# ProPrj_1111_2025-11-28.net
KiCad netlist of a schematic drawn in EasyEDA Pro
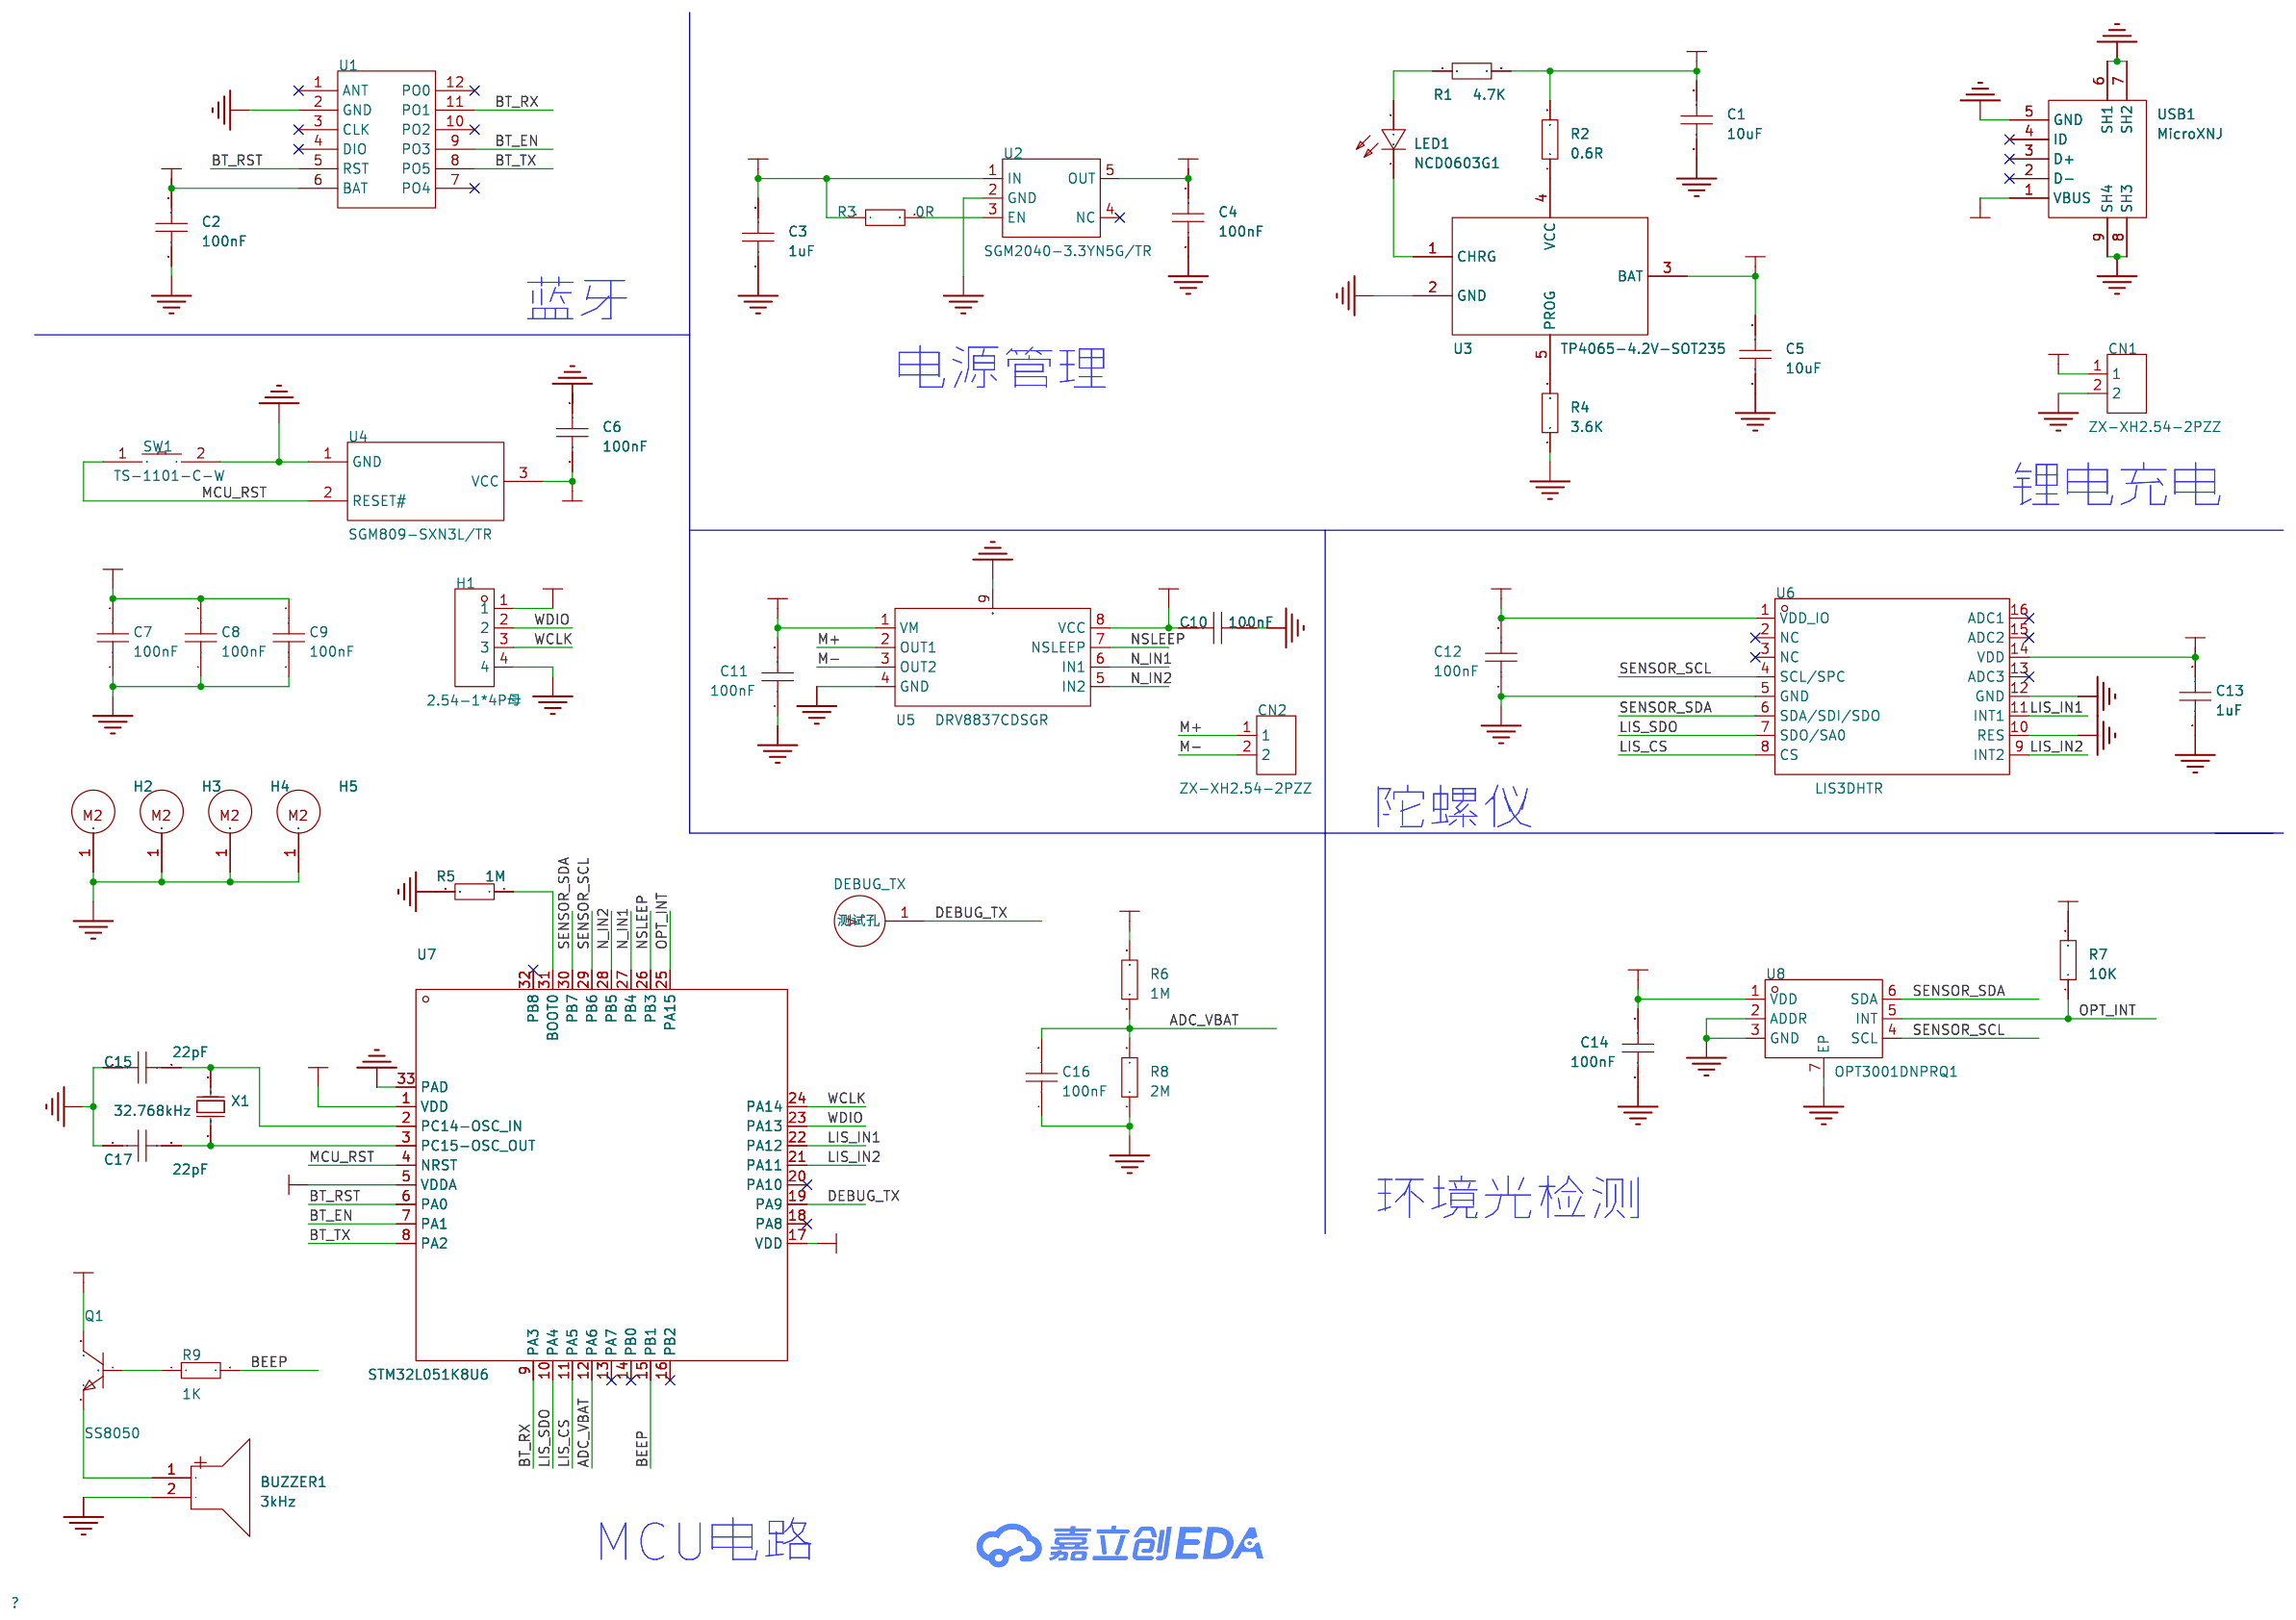
[diagram p0: schematic sheet]

(export (version "E")
  (design (tool "Eeschema 10.0.6"))
  (components
    (comp (ref "BUZZER1")
      (value "3kHz")
      (footprint "easyedapro:BUZ-TH_BD9.0-P5.00-D0.6-FD")
      (description "驱动方式:有源(内含驱动线路);构造类型:电磁式;频率:3kHz;声压(SPL):85dB;")
      (fields (field (name "Manufacturer Part") "HNB09A03") (field (name "Manufacturer") "华能"))
      (libsource (lib "easyedapro") (part "HNB09A03"))
    )
    (comp (ref "C1")
      (value "10uF")
      (footprint "easyedapro:C0603")
      (libsource (lib "easyedapro") (part "Capacitance"))
    )
    (comp (ref "C2")
      (value "100nF")
      (footprint "easyedapro:C0603")
      (libsource (lib "easyedapro") (part "Capacitance"))
    )
    (comp (ref "C3")
      (value "1uF")
      (footprint "easyedapro:C0603")
      (libsource (lib "easyedapro") (part "Capacitance"))
    )
    (comp (ref "C4")
      (value "100nF")
      (footprint "easyedapro:C0603")
      (libsource (lib "easyedapro") (part "Capacitance"))
    )
    (comp (ref "C5")
      (value "10uF")
      (footprint "easyedapro:C0603")
      (libsource (lib "easyedapro") (part "Capacitance"))
    )
    (comp (ref "C6")
      (value "100nF")
      (footprint "easyedapro:C0603")
      (libsource (lib "easyedapro") (part "Capacitance"))
    )
    (comp (ref "C7")
      (value "100nF")
      (footprint "easyedapro:C0603")
      (libsource (lib "easyedapro") (part "Capacitance"))
    )
    (comp (ref "C8")
      (value "100nF")
      (footprint "easyedapro:C0603")
      (libsource (lib "easyedapro") (part "Capacitance"))
    )
    (comp (ref "C9")
      (value "100nF")
      (footprint "easyedapro:C0603")
      (libsource (lib "easyedapro") (part "Capacitance"))
    )
    (comp (ref "C10")
      (value "100nF")
      (footprint "easyedapro:C0603")
      (libsource (lib "easyedapro") (part "Capacitance"))
    )
    (comp (ref "C11")
      (value "100nF")
      (footprint "easyedapro:C0603")
      (libsource (lib "easyedapro") (part "Capacitance"))
    )
    (comp (ref "C12")
      (value "100nF")
      (footprint "easyedapro:C0603")
      (libsource (lib "easyedapro") (part "Capacitance"))
    )
    (comp (ref "C13")
      (value "1uF")
      (footprint "easyedapro:C0603")
      (libsource (lib "easyedapro") (part "Capacitance"))
    )
    (comp (ref "C14")
      (value "100nF")
      (footprint "easyedapro:C0603")
      (libsource (lib "easyedapro") (part "Capacitance"))
    )
    (comp (ref "C15")
      (value "22pF")
      (footprint "easyedapro:C0603")
      (libsource (lib "easyedapro") (part "Capacitance"))
    )
    (comp (ref "C16")
      (value "100nF")
      (footprint "easyedapro:C0603")
      (libsource (lib "easyedapro") (part "Capacitance"))
    )
    (comp (ref "C17")
      (value "22pF")
      (footprint "easyedapro:C0603")
      (libsource (lib "easyedapro") (part "Capacitance"))
    )
    (comp (ref "CN1")
      (value "ZX-XH2.54-2PZZ")
      (footprint "easyedapro:CONN-TH_2P-P2.50_HX25003-2A")
      (fields (field (name "Manufacturer") "Megastar(兆星)"))
      (libsource (lib "easyedapro") (part "ZX-XH2.54-2PZZ"))
    )
    (comp (ref "CN2")
      (value "ZX-XH2.54-2PZZ")
      (footprint "easyedapro:CONN-TH_2P-P2.50_HX25003-2A")
      (fields (field (name "Manufacturer") "Megastar(兆星)"))
      (libsource (lib "easyedapro") (part "ZX-XH2.54-2PZZ"))
    )
    (comp (ref "DEBUG_TX")
      (value "~")
      (footprint "easyedapro:测试孔")
      (libsource (lib "easyedapro") (part "测试孔"))
    )
    (comp (ref "H1")
      (value "2.54-1*4P母")
      (footprint "easyedapro:HDR-TH_4P-P2.54-V-F")
      (fields (field (name "Manufacturer") "BOOMELE(博穆精密)"))
      (libsource (lib "easyedapro") (part "2.54-1*4P母"))
    )
    (comp (ref "H2") (value "~") (footprint "easyedapro:M2螺丝孔") (libsource (lib "easyedapro") (part "M2螺丝孔")))
    (comp (ref "H3") (value "~") (footprint "easyedapro:M2螺丝孔") (libsource (lib "easyedapro") (part "M2螺丝孔")))
    (comp (ref "H4") (value "~") (footprint "easyedapro:M2螺丝孔") (libsource (lib "easyedapro") (part "M2螺丝孔")))
    (comp (ref "H5") (value "~") (footprint "easyedapro:M2螺丝孔") (libsource (lib "easyedapro") (part "M2螺丝孔")))
    (comp (ref "LED1")
      (value "NCD0603G1")
      (footprint "easyedapro:LED0603-RD_1")
      (fields (field (name "Manufacturer") "国星光电"))
      (libsource (lib "easyedapro") (part "FC-D1608UGK-520D10"))
    )
    (comp (ref "Q1")
      (value "SS8050")
      (footprint "easyedapro:SOT-23_L2.9-W1.3-P1.90-LS2.4-BR")
      (description "晶体管类型:NPN;集电极电流(Ic):1.5A;集射极击穿电压(Vceo):25V;功率(Pd):300mW;直流电流增益(hFE@Ic,Vce):120@100mA,1V;")
      (fields (field (name "Manufacturer") "MDD(辰达半导体)"))
      (libsource (lib "easyedapro") (part "SS8050_C431710"))
    )
    (comp (ref "R1") (value "4.7K") (footprint "easyedapro:R0603") (libsource (lib "easyedapro") (part "电阻")))
    (comp (ref "R2") (value "0.6R") (footprint "easyedapro:R0603") (libsource (lib "easyedapro") (part "电阻")))
    (comp (ref "R3") (value "0R") (footprint "easyedapro:R0603") (libsource (lib "easyedapro") (part "电阻")))
    (comp (ref "R4") (value "3.6K") (footprint "easyedapro:R0603") (libsource (lib "easyedapro") (part "电阻")))
    (comp (ref "R5") (value "1M") (footprint "easyedapro:R0603") (libsource (lib "easyedapro") (part "电阻")))
    (comp (ref "R6") (value "1M") (footprint "easyedapro:R0603") (libsource (lib "easyedapro") (part "电阻")))
    (comp (ref "R7") (value "10K") (footprint "easyedapro:R0603") (libsource (lib "easyedapro") (part "电阻")))
    (comp (ref "R8") (value "2M") (footprint "easyedapro:R0603") (libsource (lib "easyedapro") (part "电阻")))
    (comp (ref "R9") (value "1K") (footprint "easyedapro:R0603") (libsource (lib "easyedapro") (part "电阻")))
    (comp (ref "SW1")
      (value "TS-1101-C-W")
      (footprint "easyedapro:SW-SMD_L6.0-W3.3-LS8.0")
      (fields (field (name "Manufacturer") "XKB Connectivity(中国星坤)"))
      (libsource (lib "easyedapro") (part "TS-1101-C-W"))
    )
    (comp (ref "U1") (value "~") (footprint "easyedapro:pw02") (libsource (lib "easyedapro") (part "pw02")))
    (comp (ref "U2")
      (value "SGM2040-3.3YN5G/TR")
      (footprint "easyedapro:SOT-23-5_L2.9-W1.6-P0.95-LS2.8-BL")
      (fields (field (name "Manufacturer") "SGMICRO(圣邦微)"))
      (libsource (lib "easyedapro") (part "SGM2040-3.3YN5G/TR"))
    )
    (comp (ref "U3")
      (value "TP4065-4.2V-SOT235")
      (footprint "easyedapro:SOT-23-5_L3.0-W1.7-P0.95-LS2.8-BR")
      (description "3mA-600mA 线性锂离子电池充电器")
      (fields (field (name "Manufacturer") "TOPPOWER(南京拓微)"))
      (libsource (lib "easyedapro") (part "TP4065"))
    )
    (comp (ref "U4")
      (value "SGM809-SXN3L/TR")
      (footprint "easyedapro:SOT-23-3_L2.9-W1.6-P1.90-LS2.8-BR")
      (description "工作电压:1.2V~5.5V;复位有效电平:低电平有效;受监控电压数:1;复位超时:240ms;")
      (fields (field (name "Manufacturer") "SGMICRO(圣邦微)"))
      (libsource (lib "easyedapro") (part "SGM809-SXN3L/TR"))
    )
    (comp (ref "U5")
      (value "DRV8837CDSGR")
      (footprint "easyedapro:WSON-8_L2.0-W2.0-P0.50-TL-EP")
      (description "DRV8837C 12V、1A H 桥电机驱动器")
      (fields (field (name "Manufacturer") "TI(德州仪器)"))
      (libsource (lib "easyedapro") (part "DRV8837CDSGR"))
    )
    (comp (ref "U6")
      (value "LIS3DHTR")
      (footprint "easyedapro:LGA-16_L3.0-W3.0-P0.50-TL")
      (description "3轴MEMS加速度计，超低功耗，±2g/±4g/±8g/±16g满量程，高速I2C/SPI数字输出，内置FIFO和高性能加速度传感器，LLGA 16 3x3x1.0封装")
      (fields (field (name "Manufacturer") "ST(意法半导体)"))
      (libsource (lib "easyedapro") (part "LIS3DHTR_C15134"))
    )
    (comp (ref "U7")
      (value "STM32L051K8U6")
      (footprint "easyedapro:UFQFPN-32_L5.0-W5.0-P0.50-BL-EP")
      (description "CPU内核:ARM-M系列;CPU最大主频:32MHz;应用领域:-;")
      (fields (field (name "Manufacturer") "ST(意法半导体)"))
      (libsource (lib "easyedapro") (part "STM32L051K8U6"))
    )
    (comp (ref "U8")
      (value "OPT3001DNPRQ1")
      (footprint "easyedapro:TDFN-6_L2.0-W2.0-P0.65-TL-EP1.4")
      (description "OPT3001-Q1 具有高精度人眼响应功能的汽车数字环境光传感器 (ALS)")
      (fields (field (name "Manufacturer") "TI(德州仪器)"))
      (libsource (lib "easyedapro") (part "OPT3001DNPRQ1"))
    )
    (comp (ref "USB1")
      (value "MicroXNJ")
      (footprint "easyedapro:MICRO-USB-SMD_MICROXNJ")
      (description "连接器类型:Micro-B;协议标准:USB 2.0;公母:母;安装方式:卧贴;触点数量:5P;端口数量:1;额定电流 - 电源:1.8A;工作温度:-20°C~+85°C;")
      (fields (field (name "Manufacturer") "SHOU HAN(首韩)"))
      (libsource (lib "easyedapro") (part "MICROXNJ"))
    )
    (comp (ref "X1")
      (value "32.768kHz")
      (footprint "easyedapro:CRYSTAL-SMD_L3.2-W1.5-1")
      (description "晶振类型:贴片晶振;频率:32.768kHz;常温频差:±20ppm;负载电容:12.5pF;频率稳定度:±30ppm;")
      (fields
        (field (name "Manufacturer Part") "XKXGI-SUA-32.768K")
        (field (name "Manufacturer") "YXC(扬兴晶振)")
      )
      (libsource (lib "easyedapro") (part "XKXGI-SUA-32.768K"))
    )
  )
  (nets
    (net (code "1") (name "/ADC_VBAT") (class "Default")
      (node (ref "C16") (pin "2") (pinfunction "2_2") (pintype "input"))
      (node (ref "R6") (pin "1") (pinfunction "1_1") (pintype "input"))
      (node (ref "R8") (pin "2") (pinfunction "2_2") (pintype "input"))
      (node (ref "U7") (pin "12") (pinfunction "PA6_12") (pintype "unspecified"))
    )
    (net (code "2") (name "/BEEP") (class "Default")
      (node (ref "R9") (pin "2") (pinfunction "2_2") (pintype "input"))
      (node (ref "U7") (pin "15") (pinfunction "PB1_15") (pintype "unspecified"))
    )
    (net (code "3") (name "/BT_EN") (class "Default")
      (node (ref "U1") (pin "9") (pinfunction "PO3_9") (pintype "input"))
      (node (ref "U7") (pin "7") (pinfunction "PA1_7") (pintype "unspecified"))
    )
    (net (code "4") (name "/BT_RST") (class "Default")
      (node (ref "U1") (pin "5") (pinfunction "RST_5") (pintype "input"))
      (node (ref "U7") (pin "6") (pinfunction "PA0_6") (pintype "unspecified"))
    )
    (net (code "5") (name "/BT_RX") (class "Default")
      (node (ref "U1") (pin "11") (pinfunction "PO1_11") (pintype "input"))
      (node (ref "U7") (pin "9") (pinfunction "PA3_9") (pintype "unspecified"))
    )
    (net (code "6") (name "/BT_TX") (class "Default")
      (node (ref "U1") (pin "8") (pinfunction "PO5_8") (pintype "input"))
      (node (ref "U7") (pin "8") (pinfunction "PA2_8") (pintype "unspecified"))
    )
    (net (code "7") (name "/DEBUG_TX") (class "Default")
      (node (ref "DEBUG_TX") (pin "1") (pinfunction "测试孔_1") (pintype "input"))
      (node (ref "U7") (pin "19") (pinfunction "PA9_19") (pintype "unspecified"))
    )
    (net (code "8") (name "/LIS_CS") (class "Default")
      (node (ref "U6") (pin "8") (pinfunction "CS_8") (pintype "unspecified"))
      (node (ref "U7") (pin "11") (pinfunction "PA5_11") (pintype "unspecified"))
    )
    (net (code "9") (name "/LIS_IN1") (class "Default")
      (node (ref "U6") (pin "11") (pinfunction "INT1_11") (pintype "unspecified"))
      (node (ref "U7") (pin "22") (pinfunction "PA12_22") (pintype "unspecified"))
    )
    (net (code "10") (name "/LIS_IN2") (class "Default")
      (node (ref "U6") (pin "9") (pinfunction "INT2_9") (pintype "unspecified"))
      (node (ref "U7") (pin "21") (pinfunction "PA11_21") (pintype "unspecified"))
    )
    (net (code "11") (name "/LIS_SDO") (class "Default")
      (node (ref "U6") (pin "7") (pinfunction "SDO/SA0_7") (pintype "unspecified"))
      (node (ref "U7") (pin "10") (pinfunction "PA4_10") (pintype "unspecified"))
    )
    (net (code "12") (name "/M+") (class "Default")
      (node (ref "CN2") (pin "1") (pinfunction "1_1") (pintype "unspecified"))
      (node (ref "U5") (pin "2") (pinfunction "OUT1_2") (pintype "unspecified"))
    )
    (net (code "13") (name "/M-") (class "Default")
      (node (ref "CN2") (pin "2") (pinfunction "2_2") (pintype "unspecified"))
      (node (ref "U5") (pin "3") (pinfunction "OUT2_3") (pintype "unspecified"))
    )
    (net (code "14") (name "/MCU_RST") (class "Default")
      (node (ref "SW1") (pin "1") (pinfunction "1_1") (pintype "unspecified"))
      (node (ref "U4") (pin "2") (pinfunction "RESET#_2") (pintype "unspecified"))
      (node (ref "U7") (pin "4") (pinfunction "NRST_4") (pintype "unspecified"))
    )
    (net (code "15") (name "/NSLEEP") (class "Default")
      (node (ref "U5") (pin "7") (pinfunction "NSLEEP_7") (pintype "unspecified"))
      (node (ref "U7") (pin "26") (pinfunction "PB3_26") (pintype "unspecified"))
    )
    (net (code "16") (name "/N_IN1") (class "Default")
      (node (ref "U5") (pin "6") (pinfunction "IN1_6") (pintype "unspecified"))
      (node (ref "U7") (pin "27") (pinfunction "PB4_27") (pintype "unspecified"))
    )
    (net (code "17") (name "/N_IN2") (class "Default")
      (node (ref "U5") (pin "5") (pinfunction "IN2_5") (pintype "unspecified"))
      (node (ref "U7") (pin "28") (pinfunction "PB5_28") (pintype "unspecified"))
    )
    (net (code "18") (name "/OPT_INT") (class "Default")
      (node (ref "R7") (pin "1") (pinfunction "1_1") (pintype "input"))
      (node (ref "U7") (pin "25") (pinfunction "PA15_25") (pintype "unspecified"))
      (node (ref "U8") (pin "5") (pinfunction "INT_5") (pintype "unspecified"))
    )
    (net (code "19") (name "/SENSOR_SCL") (class "Default")
      (node (ref "U6") (pin "4") (pinfunction "SCL/SPC_4") (pintype "unspecified"))
      (node (ref "U7") (pin "29") (pinfunction "PB6_29") (pintype "unspecified"))
      (node (ref "U8") (pin "4") (pinfunction "SCL_4") (pintype "unspecified"))
    )
    (net (code "20") (name "/SENSOR_SDA") (class "Default")
      (node (ref "U6") (pin "6") (pinfunction "SDA/SDI/SDO_6") (pintype "unspecified"))
      (node (ref "U7") (pin "30") (pinfunction "PB7_30") (pintype "unspecified"))
      (node (ref "U8") (pin "6") (pinfunction "SDA_6") (pintype "unspecified"))
    )
    (net (code "21") (name "/WCLK") (class "Default")
      (node (ref "H1") (pin "3") (pinfunction "3_3") (pintype "unspecified"))
      (node (ref "U7") (pin "24") (pinfunction "PA14_24") (pintype "unspecified"))
    )
    (net (code "22") (name "/WDIO") (class "Default")
      (node (ref "H1") (pin "2") (pinfunction "2_2") (pintype "unspecified"))
      (node (ref "U7") (pin "23") (pinfunction "PA13_23") (pintype "unspecified"))
    )
    (net (code "23") (name "DC3.3V") (class "Default")
      (node (ref "C10") (pin "2") (pinfunction "2_2") (pintype "input"))
      (node (ref "C12") (pin "2") (pinfunction "2_2") (pintype "input"))
      (node (ref "C13") (pin "2") (pinfunction "2_2") (pintype "input"))
      (node (ref "C14") (pin "2") (pinfunction "2_2") (pintype "input"))
      (node (ref "C2") (pin "2") (pinfunction "2_2") (pintype "input"))
      (node (ref "C4") (pin "2") (pinfunction "2_2") (pintype "input"))
      (node (ref "C6") (pin "2") (pinfunction "2_2") (pintype "input"))
      (node (ref "C7") (pin "2") (pinfunction "2_2") (pintype "input"))
      (node (ref "C8") (pin "2") (pinfunction "2_2") (pintype "input"))
      (node (ref "C9") (pin "2") (pinfunction "2_2") (pintype "input"))
      (node (ref "H1") (pin "1") (pinfunction "1_1") (pintype "unspecified"))
      (node (ref "Q1") (pin "3") (pinfunction "C_3") (pintype "unspecified"))
      (node (ref "R7") (pin "2") (pinfunction "2_2") (pintype "input"))
      (node (ref "U1") (pin "6") (pinfunction "BAT_6") (pintype "input"))
      (node (ref "U2") (pin "5") (pinfunction "OUT_5") (pintype "unspecified"))
      (node (ref "U4") (pin "3") (pinfunction "VCC_3") (pintype "unspecified"))
      (node (ref "U5") (pin "8") (pinfunction "VCC_8") (pintype "unspecified"))
      (node (ref "U6") (pin "1") (pinfunction "VDD_IO_1") (pintype "unspecified"))
      (node (ref "U6") (pin "14") (pinfunction "VDD_14") (pintype "unspecified"))
      (node (ref "U7") (pin "1") (pinfunction "VDD_1") (pintype "unspecified"))
      (node (ref "U7") (pin "17") (pinfunction "VDD_17") (pintype "unspecified"))
      (node (ref "U7") (pin "5") (pinfunction "VDDA_5") (pintype "unspecified"))
      (node (ref "U8") (pin "1") (pinfunction "VDD_1") (pintype "unspecified"))
    )
    (net (code "24") (name "GND") (class "Default")
      (node (ref "BUZZER1") (pin "2") (pinfunction "-_2") (pintype "unspecified"))
      (node (ref "C1") (pin "1") (pinfunction "1_1") (pintype "input"))
      (node (ref "C10") (pin "1") (pinfunction "1_1") (pintype "input"))
      (node (ref "C11") (pin "1") (pinfunction "1_1") (pintype "input"))
      (node (ref "C12") (pin "1") (pinfunction "1_1") (pintype "input"))
      (node (ref "C13") (pin "1") (pinfunction "1_1") (pintype "input"))
      (node (ref "C14") (pin "1") (pinfunction "1_1") (pintype "input"))
      (node (ref "C15") (pin "1") (pinfunction "1_1") (pintype "input"))
      (node (ref "C16") (pin "1") (pinfunction "1_1") (pintype "input"))
      (node (ref "C17") (pin "1") (pinfunction "1_1") (pintype "input"))
      (node (ref "C2") (pin "1") (pinfunction "1_1") (pintype "input"))
      (node (ref "C3") (pin "1") (pinfunction "1_1") (pintype "input"))
      (node (ref "C4") (pin "1") (pinfunction "1_1") (pintype "input"))
      (node (ref "C5") (pin "1") (pinfunction "1_1") (pintype "input"))
      (node (ref "C6") (pin "1") (pinfunction "1_1") (pintype "input"))
      (node (ref "C7") (pin "1") (pinfunction "1_1") (pintype "input"))
      (node (ref "C8") (pin "1") (pinfunction "1_1") (pintype "input"))
      (node (ref "C9") (pin "1") (pinfunction "1_1") (pintype "input"))
      (node (ref "CN1") (pin "2") (pinfunction "2_2") (pintype "unspecified"))
      (node (ref "H1") (pin "4") (pinfunction "4_4") (pintype "unspecified"))
      (node (ref "H2") (pin "1") (pinfunction "1_1") (pintype "input"))
      (node (ref "H3") (pin "1") (pinfunction "1_1") (pintype "input"))
      (node (ref "H4") (pin "1") (pinfunction "1_1") (pintype "input"))
      (node (ref "H5") (pin "1") (pinfunction "1_1") (pintype "input"))
      (node (ref "R4") (pin "1") (pinfunction "1_1") (pintype "input"))
      (node (ref "R5") (pin "2") (pinfunction "2_2") (pintype "input"))
      (node (ref "R8") (pin "1") (pinfunction "1_1") (pintype "input"))
      (node (ref "SW1") (pin "2") (pinfunction "2_2") (pintype "unspecified"))
      (node (ref "U1") (pin "2") (pinfunction "GND_2") (pintype "input"))
      (node (ref "U2") (pin "2") (pinfunction "GND_2") (pintype "unspecified"))
      (node (ref "U3") (pin "2") (pinfunction "GND_2") (pintype "unspecified"))
      (node (ref "U4") (pin "1") (pinfunction "GND_1") (pintype "unspecified"))
      (node (ref "U5") (pin "4") (pinfunction "GND_4") (pintype "unspecified"))
      (node (ref "U5") (pin "9") (pinfunction "PAD_9") (pintype "unspecified"))
      (node (ref "U6") (pin "10") (pinfunction "RES_10") (pintype "unspecified"))
      (node (ref "U6") (pin "12") (pinfunction "GND_12") (pintype "unspecified"))
      (node (ref "U6") (pin "5") (pinfunction "GND_5") (pintype "unspecified"))
      (node (ref "U7") (pin "33") (pinfunction "PAD_33") (pintype "unspecified"))
      (node (ref "U8") (pin "2") (pinfunction "ADDR_2") (pintype "unspecified"))
      (node (ref "U8") (pin "3") (pinfunction "GND_3") (pintype "unspecified"))
      (node (ref "U8") (pin "7") (pinfunction "EP_7") (pintype "unspecified"))
      (node (ref "USB1") (pin "5") (pinfunction "GND_5") (pintype "unspecified"))
      (node (ref "USB1") (pin "6") (pinfunction "SH1_6") (pintype "unspecified"))
      (node (ref "USB1") (pin "7") (pinfunction "SH2_7") (pintype "unspecified"))
      (node (ref "USB1") (pin "8") (pinfunction "SH3_8") (pintype "unspecified"))
      (node (ref "USB1") (pin "9") (pinfunction "SH4_9") (pintype "unspecified"))
    )
    (net (code "25") (name "Net-(BUZZER1-+)") (class "Default")
      (node (ref "BUZZER1") (pin "1") (pinfunction "+_1") (pintype "unspecified"))
      (node (ref "Q1") (pin "2") (pinfunction "E_2") (pintype "unspecified"))
    )
    (net (code "26") (name "Net-(LED1-A)") (class "Default")
      (node (ref "LED1") (pin "2") (pinfunction "A_2") (pintype "input"))
      (node (ref "R1") (pin "2") (pinfunction "2_2") (pintype "input"))
    )
    (net (code "27") (name "Net-(LED1-K)") (class "Default")
      (node (ref "LED1") (pin "1") (pinfunction "K_1") (pintype "input"))
      (node (ref "U3") (pin "1") (pinfunction "CHRG_1") (pintype "unspecified"))
    )
    (net (code "28") (name "Net-(Q1-B)") (class "Default")
      (node (ref "Q1") (pin "1") (pinfunction "B_1") (pintype "unspecified"))
      (node (ref "R9") (pin "1") (pinfunction "1_1") (pintype "input"))
    )
    (net (code "29") (name "Net-(U2-EN)") (class "Default")
      (node (ref "R3") (pin "2") (pinfunction "2_2") (pintype "input"))
      (node (ref "U2") (pin "3") (pinfunction "EN_3") (pintype "unspecified"))
    )
    (net (code "30") (name "Net-(U3-PROG)") (class "Default")
      (node (ref "R4") (pin "2") (pinfunction "2_2") (pintype "input"))
      (node (ref "U3") (pin "5") (pinfunction "PROG_5") (pintype "unspecified"))
    )
    (net (code "31") (name "Net-(U3-VCC)") (class "Default")
      (node (ref "R2") (pin "1") (pinfunction "1_1") (pintype "input"))
      (node (ref "U3") (pin "4") (pinfunction "VCC_4") (pintype "unspecified"))
    )
    (net (code "32") (name "Net-(U7-BOOT0)") (class "Default")
      (node (ref "R5") (pin "1") (pinfunction "1_1") (pintype "input"))
      (node (ref "U7") (pin "31") (pinfunction "BOOT0_31") (pintype "unspecified"))
    )
    (net (code "33") (name "Net-(U7-PC14-OSC_IN)") (class "Default")
      (node (ref "C15") (pin "2") (pinfunction "2_2") (pintype "input"))
      (node (ref "U7") (pin "2") (pinfunction "PC14-OSC_IN_2") (pintype "unspecified"))
      (node (ref "X1") (pin "2") (pinfunction "OSC2_2") (pintype "input"))
    )
    (net (code "34") (name "Net-(U7-PC15-OSC_OUT)") (class "Default")
      (node (ref "C17") (pin "2") (pinfunction "2_2") (pintype "input"))
      (node (ref "U7") (pin "3") (pinfunction "PC15-OSC_OUT_3") (pintype "unspecified"))
      (node (ref "X1") (pin "1") (pinfunction "OSC1_1") (pintype "input"))
    )
    (net (code "35") (name "VBAT") (class "Default")
      (node (ref "C11") (pin "2") (pinfunction "2_2") (pintype "input"))
      (node (ref "C3") (pin "2") (pinfunction "2_2") (pintype "input"))
      (node (ref "C5") (pin "2") (pinfunction "2_2") (pintype "input"))
      (node (ref "CN1") (pin "1") (pinfunction "1_1") (pintype "unspecified"))
      (node (ref "R3") (pin "1") (pinfunction "1_1") (pintype "input"))
      (node (ref "R6") (pin "2") (pinfunction "2_2") (pintype "input"))
      (node (ref "U2") (pin "1") (pinfunction "IN_1") (pintype "unspecified"))
      (node (ref "U3") (pin "3") (pinfunction "BAT_3") (pintype "unspecified"))
      (node (ref "U5") (pin "1") (pinfunction "VM_1") (pintype "unspecified"))
    )
    (net (code "36") (name "VUSB") (class "Default")
      (node (ref "C1") (pin "2") (pinfunction "2_2") (pintype "input"))
      (node (ref "R1") (pin "1") (pinfunction "1_1") (pintype "input"))
      (node (ref "R2") (pin "2") (pinfunction "2_2") (pintype "input"))
      (node (ref "USB1") (pin "1") (pinfunction "VBUS_1") (pintype "unspecified"))
    )
    (net (code "37") (name "unconnected-(U1-ANT-Pad1)") (class "Default")
      (node (ref "U1") (pin "1") (pinfunction "ANT_1") (pintype "input+no_connect"))
    )
    (net (code "38") (name "unconnected-(U1-CLK-Pad3)") (class "Default")
      (node (ref "U1") (pin "3") (pinfunction "CLK_3") (pintype "input+no_connect"))
    )
    (net (code "39") (name "unconnected-(U1-DIO-Pad4)") (class "Default")
      (node (ref "U1") (pin "4") (pinfunction "DIO_4") (pintype "input+no_connect"))
    )
    (net (code "40") (name "unconnected-(U1-PO0-Pad12)") (class "Default")
      (node (ref "U1") (pin "12") (pinfunction "PO0_12") (pintype "input+no_connect"))
    )
    (net (code "41") (name "unconnected-(U1-PO2-Pad10)") (class "Default")
      (node (ref "U1") (pin "10") (pinfunction "PO2_10") (pintype "input+no_connect"))
    )
    (net (code "42") (name "unconnected-(U1-PO4-Pad7)") (class "Default")
      (node (ref "U1") (pin "7") (pinfunction "PO4_7") (pintype "input+no_connect"))
    )
    (net (code "43") (name "unconnected-(U2-NC-Pad4)") (class "Default")
      (node (ref "U2") (pin "4") (pinfunction "NC_4") (pintype "unspecified+no_connect"))
    )
    (net (code "44") (name "unconnected-(U6-ADC1-Pad16)") (class "Default")
      (node (ref "U6") (pin "16") (pinfunction "ADC1_16") (pintype "unspecified+no_connect"))
    )
    (net (code "45") (name "unconnected-(U6-ADC2-Pad15)") (class "Default")
      (node (ref "U6") (pin "15") (pinfunction "ADC2_15") (pintype "unspecified+no_connect"))
    )
    (net (code "46") (name "unconnected-(U6-ADC3-Pad13)") (class "Default")
      (node (ref "U6") (pin "13") (pinfunction "ADC3_13") (pintype "unspecified+no_connect"))
    )
    (net (code "47") (name "unconnected-(U6-NC-Pad2)") (class "Default")
      (node (ref "U6") (pin "2") (pinfunction "NC_2") (pintype "unspecified+no_connect"))
    )
    (net (code "48") (name "unconnected-(U6-NC-Pad3)") (class "Default")
      (node (ref "U6") (pin "3") (pinfunction "NC_3") (pintype "unspecified+no_connect"))
    )
    (net (code "49") (name "unconnected-(U7-PA7-Pad13)") (class "Default")
      (node (ref "U7") (pin "13") (pinfunction "PA7_13") (pintype "unspecified+no_connect"))
    )
    (net (code "50") (name "unconnected-(U7-PA8-Pad18)") (class "Default")
      (node (ref "U7") (pin "18") (pinfunction "PA8_18") (pintype "unspecified+no_connect"))
    )
    (net (code "51") (name "unconnected-(U7-PA10-Pad20)") (class "Default")
      (node (ref "U7") (pin "20") (pinfunction "PA10_20") (pintype "unspecified+no_connect"))
    )
    (net (code "52") (name "unconnected-(U7-PB0-Pad14)") (class "Default")
      (node (ref "U7") (pin "14") (pinfunction "PB0_14") (pintype "unspecified+no_connect"))
    )
    (net (code "53") (name "unconnected-(U7-PB2-Pad16)") (class "Default")
      (node (ref "U7") (pin "16") (pinfunction "PB2_16") (pintype "unspecified+no_connect"))
    )
    (net (code "54") (name "unconnected-(U7-PB8-Pad32)") (class "Default")
      (node (ref "U7") (pin "32") (pinfunction "PB8_32") (pintype "unspecified+no_connect"))
    )
    (net (code "55") (name "unconnected-(USB1-D+-Pad3)") (class "Default")
      (node (ref "USB1") (pin "3") (pinfunction "D+_3") (pintype "unspecified+no_connect"))
    )
    (net (code "56") (name "unconnected-(USB1-D--Pad2)") (class "Default")
      (node (ref "USB1") (pin "2") (pinfunction "D-_2") (pintype "unspecified+no_connect"))
    )
    (net (code "57") (name "unconnected-(USB1-ID-Pad4)") (class "Default")
      (node (ref "USB1") (pin "4") (pinfunction "ID_4") (pintype "unspecified+no_connect"))
    )
  )
)
